# KEY.net
KiCad netlist of a schematic drawn in Altium Designer
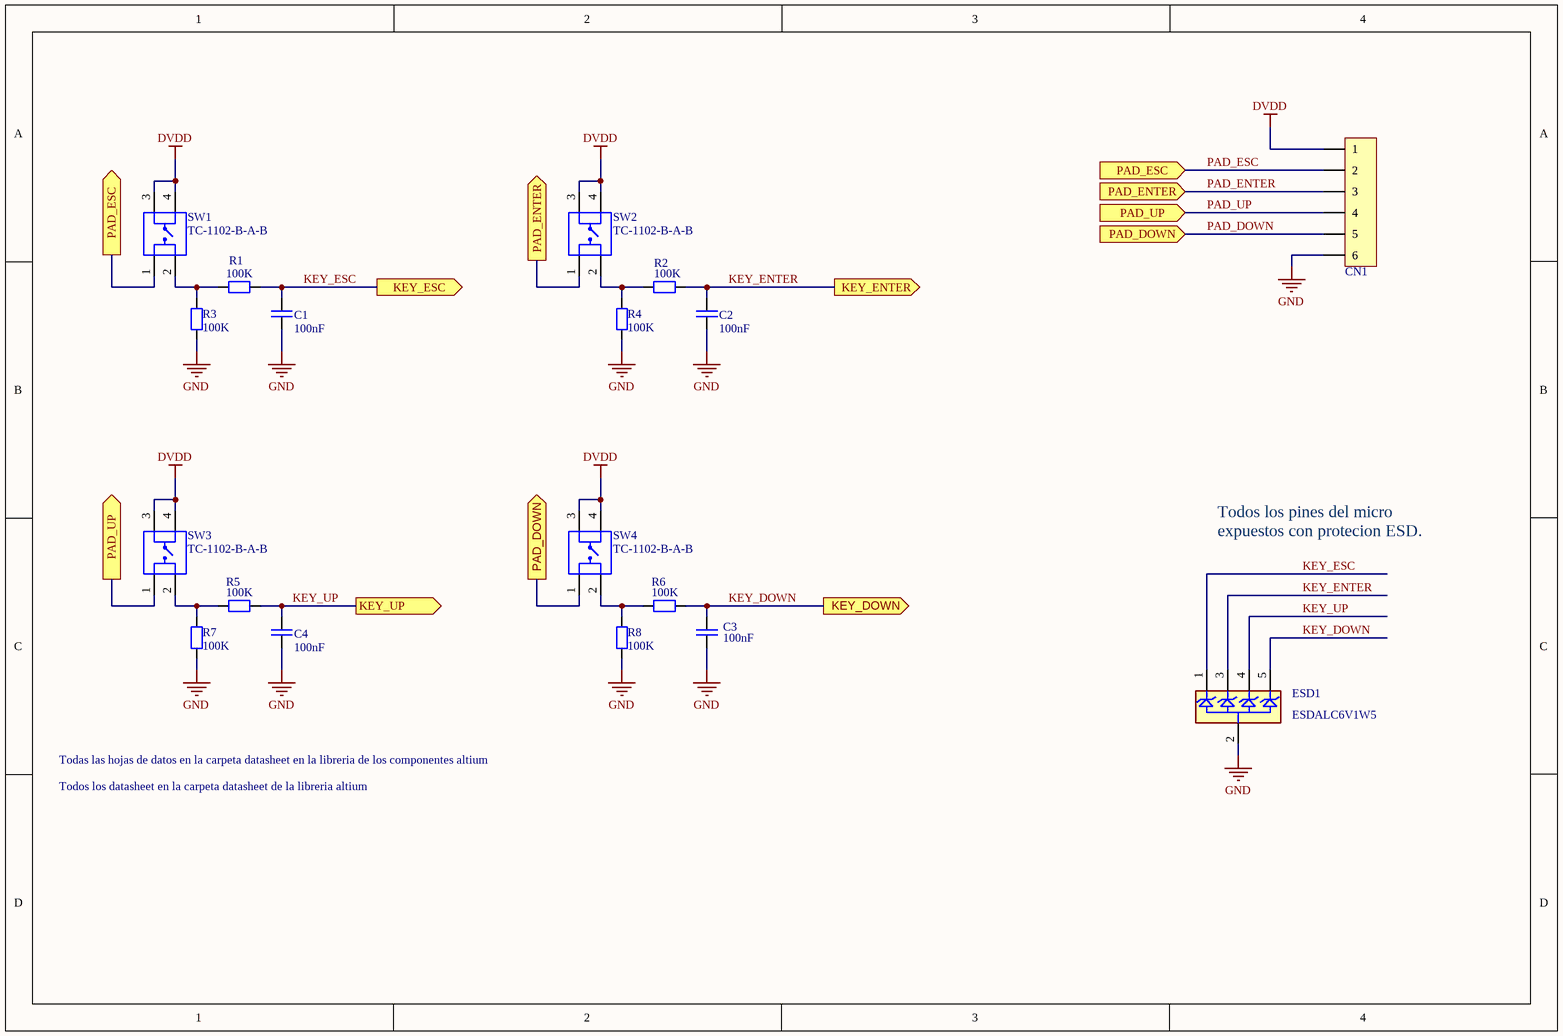
[diagram p0: KEY.SchDoc]

(export (version "E")
  (design (tool "Eeschema 10.0.6"))
  (components
    (comp (ref "C1")
      (value "100nF")
      (footprint "CAP_SM0805_YAGEOCC2_N")
      (description "CAP 100nF SM0805 X7R 25V YAGEO CC2")
      (fields
        (field (name "MANUFACTURER") "Yageo")
        (field (name "MANUFACTURER PART NUMBER") "CC0805KRX7R8BB104")
      )
      (libsource (lib "Yageo") (part "CC0805KRX7R8BB104"))
    )
    (comp (ref "C2")
      (value "100nF")
      (footprint "CAP_SM0805_YAGEOCC2_N")
      (description "CAP 100nF SM0805 X7R 25V YAGEO CC2")
      (fields
        (field (name "MANUFACTURER") "Yageo")
        (field (name "MANUFACTURER PART NUMBER") "CC0805KRX7R8BB104")
      )
      (libsource (lib "Yageo") (part "CC0805KRX7R8BB104"))
    )
    (comp (ref "C3")
      (value "100nF")
      (footprint "CAP_SM0805_YAGEOCC2_N")
      (description "CAP 100nF SM0805 X7R 25V YAGEO CC2")
      (fields
        (field (name "MANUFACTURER") "Yageo")
        (field (name "MANUFACTURER PART NUMBER") "CC0805KRX7R8BB104")
      )
      (libsource (lib "Yageo") (part "CC0805KRX7R8BB104"))
    )
    (comp (ref "C4")
      (value "100nF")
      (footprint "CAP_SM0805_YAGEOCC2_N")
      (description "CAP 100nF SM0805 X7R 25V YAGEO CC2")
      (fields
        (field (name "MANUFACTURER") "Yageo")
        (field (name "MANUFACTURER PART NUMBER") "CC0805KRX7R8BB104")
      )
      (libsource (lib "Yageo") (part "CC0805KRX7R8BB104"))
    )
    (comp (ref "CN1")
      (value "PH2.54-07-06PWD")
      (footprint "HEADER PIN 1X6 A 90 GRADOS")
      (description "1 x 6 - true hole  2.54mm - Pb free - 90°")
      (fields (field (name "MANUFACTURER") "XUNPU"))
      (libsource (lib "header_pin") (part "PH2.54-07-06PWD"))
    )
    (comp (ref "ESD1")
      (value "ESDALC6V1W5")
      (footprint "ESDALC6V1W5")
      (fields (field (name "MANUFACTURER") "ST"))
      (libsource (lib "diode") (part "ESDALC6V1W5"))
    )
    (comp (ref "R1")
      (value "100K")
      (footprint "RES_SM0805_YAGEORC_N")
      (description "RES 100K SM0805 YAGEO RC_L")
      (fields
        (field (name "MANUFACTURER") "Yageo")
        (field (name "MANUFACTURER PART NUMBER") "RC0805FR-07100KL")
      )
      (libsource (lib "") (part "RC0805FR-07100KL_1"))
    )
    (comp (ref "R2")
      (value "100K")
      (footprint "RES_SM0805_YAGEORC_N")
      (description "RES 100K SM0805 YAGEO RC_L")
      (fields
        (field (name "MANUFACTURER") "Yageo")
        (field (name "MANUFACTURER PART NUMBER") "RC0805FR-07100KL")
      )
      (libsource (lib "") (part "RC0805FR-07100KL_1"))
    )
    (comp (ref "R3")
      (value "100K")
      (footprint "RES_SM0805_YAGEORC_N")
      (description "RES 100K SM0805 YAGEO RC_L")
      (fields
        (field (name "MANUFACTURER") "Yageo")
        (field (name "MANUFACTURER PART NUMBER") "RC0805FR-07100KL")
      )
      (libsource (lib "Yageo") (part "RC0805FR-07100KL"))
    )
    (comp (ref "R4")
      (value "100K")
      (footprint "RES_SM0805_YAGEORC_N")
      (description "RES 100K SM0805 YAGEO RC_L")
      (fields
        (field (name "MANUFACTURER") "Yageo")
        (field (name "MANUFACTURER PART NUMBER") "RC0805FR-07100KL")
      )
      (libsource (lib "Yageo") (part "RC0805FR-07100KL"))
    )
    (comp (ref "R5")
      (value "100K")
      (footprint "RES_SM0805_YAGEORC_N")
      (description "RES 100K SM0805 YAGEO RC_L")
      (fields
        (field (name "MANUFACTURER") "Yageo")
        (field (name "MANUFACTURER PART NUMBER") "RC0805FR-07100KL")
      )
      (libsource (lib "") (part "RC0805FR-07100KL_1"))
    )
    (comp (ref "R6")
      (value "100K")
      (footprint "RES_SM0805_YAGEORC_N")
      (description "RES 100K SM0805 YAGEO RC_L")
      (fields
        (field (name "MANUFACTURER") "Yageo")
        (field (name "MANUFACTURER PART NUMBER") "RC0805FR-07100KL")
      )
      (libsource (lib "") (part "RC0805FR-07100KL_1"))
    )
    (comp (ref "R7")
      (value "100K")
      (footprint "RES_SM0805_YAGEORC_N")
      (description "RES 100K SM0805 YAGEO RC_L")
      (fields
        (field (name "MANUFACTURER") "Yageo")
        (field (name "MANUFACTURER PART NUMBER") "RC0805FR-07100KL")
      )
      (libsource (lib "Yageo") (part "RC0805FR-07100KL"))
    )
    (comp (ref "R8")
      (value "100K")
      (footprint "RES_SM0805_YAGEORC_N")
      (description "RES 100K SM0805 YAGEO RC_L")
      (fields
        (field (name "MANUFACTURER") "Yageo")
        (field (name "MANUFACTURER PART NUMBER") "RC0805FR-07100KL")
      )
      (libsource (lib "Yageo") (part "RC0805FR-07100KL"))
    )
    (comp (ref "SW1")
      (value "TC-1102-B-A-B")
      (footprint "TC-1102-B-A-B")
      (description "Switch tactile 6x6mm true hole.")
      (fields (field (name "MANUFACTURER") "XKB Connectivity"))
      (libsource (lib "Switches") (part "TC-1102-B-A-B"))
    )
    (comp (ref "SW2")
      (value "TC-1102-B-A-B")
      (footprint "TC-1102-B-A-B")
      (description "Switch tactile 6x6mm true hole.")
      (fields (field (name "MANUFACTURER") "XKB Connectivity"))
      (libsource (lib "Switches") (part "TC-1102-B-A-B"))
    )
    (comp (ref "SW3")
      (value "TC-1102-B-A-B")
      (footprint "TC-1102-B-A-B")
      (description "Switch tactile 6x6mm true hole.")
      (fields (field (name "MANUFACTURER") "XKB Connectivity"))
      (libsource (lib "Switches") (part "TC-1102-B-A-B"))
    )
    (comp (ref "SW4")
      (value "TC-1102-B-A-B")
      (footprint "TC-1102-B-A-B")
      (description "Switch tactile 6x6mm true hole.")
      (fields (field (name "MANUFACTURER") "XKB Connectivity"))
      (libsource (lib "Switches") (part "TC-1102-B-A-B"))
    )
  )
  (nets
    (net (code "1") (name "/KEY_DOWN") (class "Default")
      (node (ref "C3") (pin "1") (pintype "passive"))
      (node (ref "ESD1") (pin "5") (pinfunction "I/04_5") (pintype "passive"))
      (node (ref "R6") (pin "2") (pintype "passive"))
    )
    (net (code "2") (name "/KEY_ENTER") (class "Default")
      (node (ref "C2") (pin "1") (pintype "passive"))
      (node (ref "ESD1") (pin "3") (pinfunction "I/02_3") (pintype "passive"))
      (node (ref "R2") (pin "2") (pintype "passive"))
    )
    (net (code "3") (name "/KEY_ESC") (class "Default")
      (node (ref "C1") (pin "1") (pintype "passive"))
      (node (ref "ESD1") (pin "1") (pinfunction "I/01_1") (pintype "passive"))
      (node (ref "R1") (pin "2") (pintype "passive"))
    )
    (net (code "4") (name "/KEY_UP") (class "Default")
      (node (ref "C4") (pin "1") (pintype "passive"))
      (node (ref "ESD1") (pin "4") (pinfunction "I/03_4") (pintype "passive"))
      (node (ref "R5") (pin "2") (pintype "passive"))
    )
    (net (code "5") (name "/PAD_DOWN") (class "Default")
      (node (ref "CN1") (pin "5") (pinfunction "5_5") (pintype "passive"))
      (node (ref "SW4") (pin "1") (pinfunction "1_1") (pintype "passive"))
    )
    (net (code "6") (name "/PAD_ENTER") (class "Default")
      (node (ref "CN1") (pin "3") (pinfunction "3_3") (pintype "passive"))
      (node (ref "SW2") (pin "1") (pinfunction "1_1") (pintype "passive"))
    )
    (net (code "7") (name "/PAD_ESC") (class "Default")
      (node (ref "CN1") (pin "2") (pinfunction "2_2") (pintype "passive"))
      (node (ref "SW1") (pin "1") (pinfunction "1_1") (pintype "passive"))
    )
    (net (code "8") (name "/PAD_UP") (class "Default")
      (node (ref "CN1") (pin "4") (pinfunction "4_4") (pintype "passive"))
      (node (ref "SW3") (pin "1") (pinfunction "1_1") (pintype "passive"))
    )
    (net (code "9") (name "DVDD") (class "Default")
      (node (ref "CN1") (pin "1") (pinfunction "1_1") (pintype "passive"))
      (node (ref "SW1") (pin "3") (pinfunction "g_3") (pintype "passive"))
      (node (ref "SW1") (pin "4") (pinfunction "4_4") (pintype "passive"))
      (node (ref "SW2") (pin "3") (pinfunction "g_3") (pintype "passive"))
      (node (ref "SW2") (pin "4") (pinfunction "4_4") (pintype "passive"))
      (node (ref "SW3") (pin "3") (pinfunction "g_3") (pintype "passive"))
      (node (ref "SW3") (pin "4") (pinfunction "4_4") (pintype "passive"))
      (node (ref "SW4") (pin "3") (pinfunction "g_3") (pintype "passive"))
      (node (ref "SW4") (pin "4") (pinfunction "4_4") (pintype "passive"))
    )
    (net (code "10") (name "GND") (class "Default")
      (node (ref "C1") (pin "2") (pintype "passive"))
      (node (ref "C2") (pin "2") (pintype "passive"))
      (node (ref "C3") (pin "2") (pintype "passive"))
      (node (ref "C4") (pin "2") (pintype "passive"))
      (node (ref "CN1") (pin "6") (pinfunction "6_6") (pintype "passive"))
      (node (ref "ESD1") (pin "2") (pinfunction "GND_2") (pintype "passive"))
      (node (ref "R3") (pin "1") (pintype "passive"))
      (node (ref "R4") (pin "1") (pintype "passive"))
      (node (ref "R7") (pin "1") (pintype "passive"))
      (node (ref "R8") (pin "1") (pintype "passive"))
    )
    (net (code "11") (name "Net-(R1-Pad1)") (class "Default")
      (node (ref "R1") (pin "1") (pintype "passive"))
      (node (ref "R3") (pin "2") (pintype "passive"))
      (node (ref "SW1") (pin "2") (pinfunction "2_2") (pintype "passive"))
    )
    (net (code "12") (name "Net-(R2-Pad1)") (class "Default")
      (node (ref "R2") (pin "1") (pintype "passive"))
      (node (ref "R4") (pin "2") (pintype "passive"))
      (node (ref "SW2") (pin "2") (pinfunction "2_2") (pintype "passive"))
    )
    (net (code "13") (name "Net-(R5-Pad1)") (class "Default")
      (node (ref "R5") (pin "1") (pintype "passive"))
      (node (ref "R7") (pin "2") (pintype "passive"))
      (node (ref "SW3") (pin "2") (pinfunction "2_2") (pintype "passive"))
    )
    (net (code "14") (name "Net-(R6-Pad1)") (class "Default")
      (node (ref "R6") (pin "1") (pintype "passive"))
      (node (ref "R8") (pin "2") (pintype "passive"))
      (node (ref "SW4") (pin "2") (pinfunction "2_2") (pintype "passive"))
    )
  )
)
